# CATv1.net
KiCad netlist of a schematic drawn in EAGLE
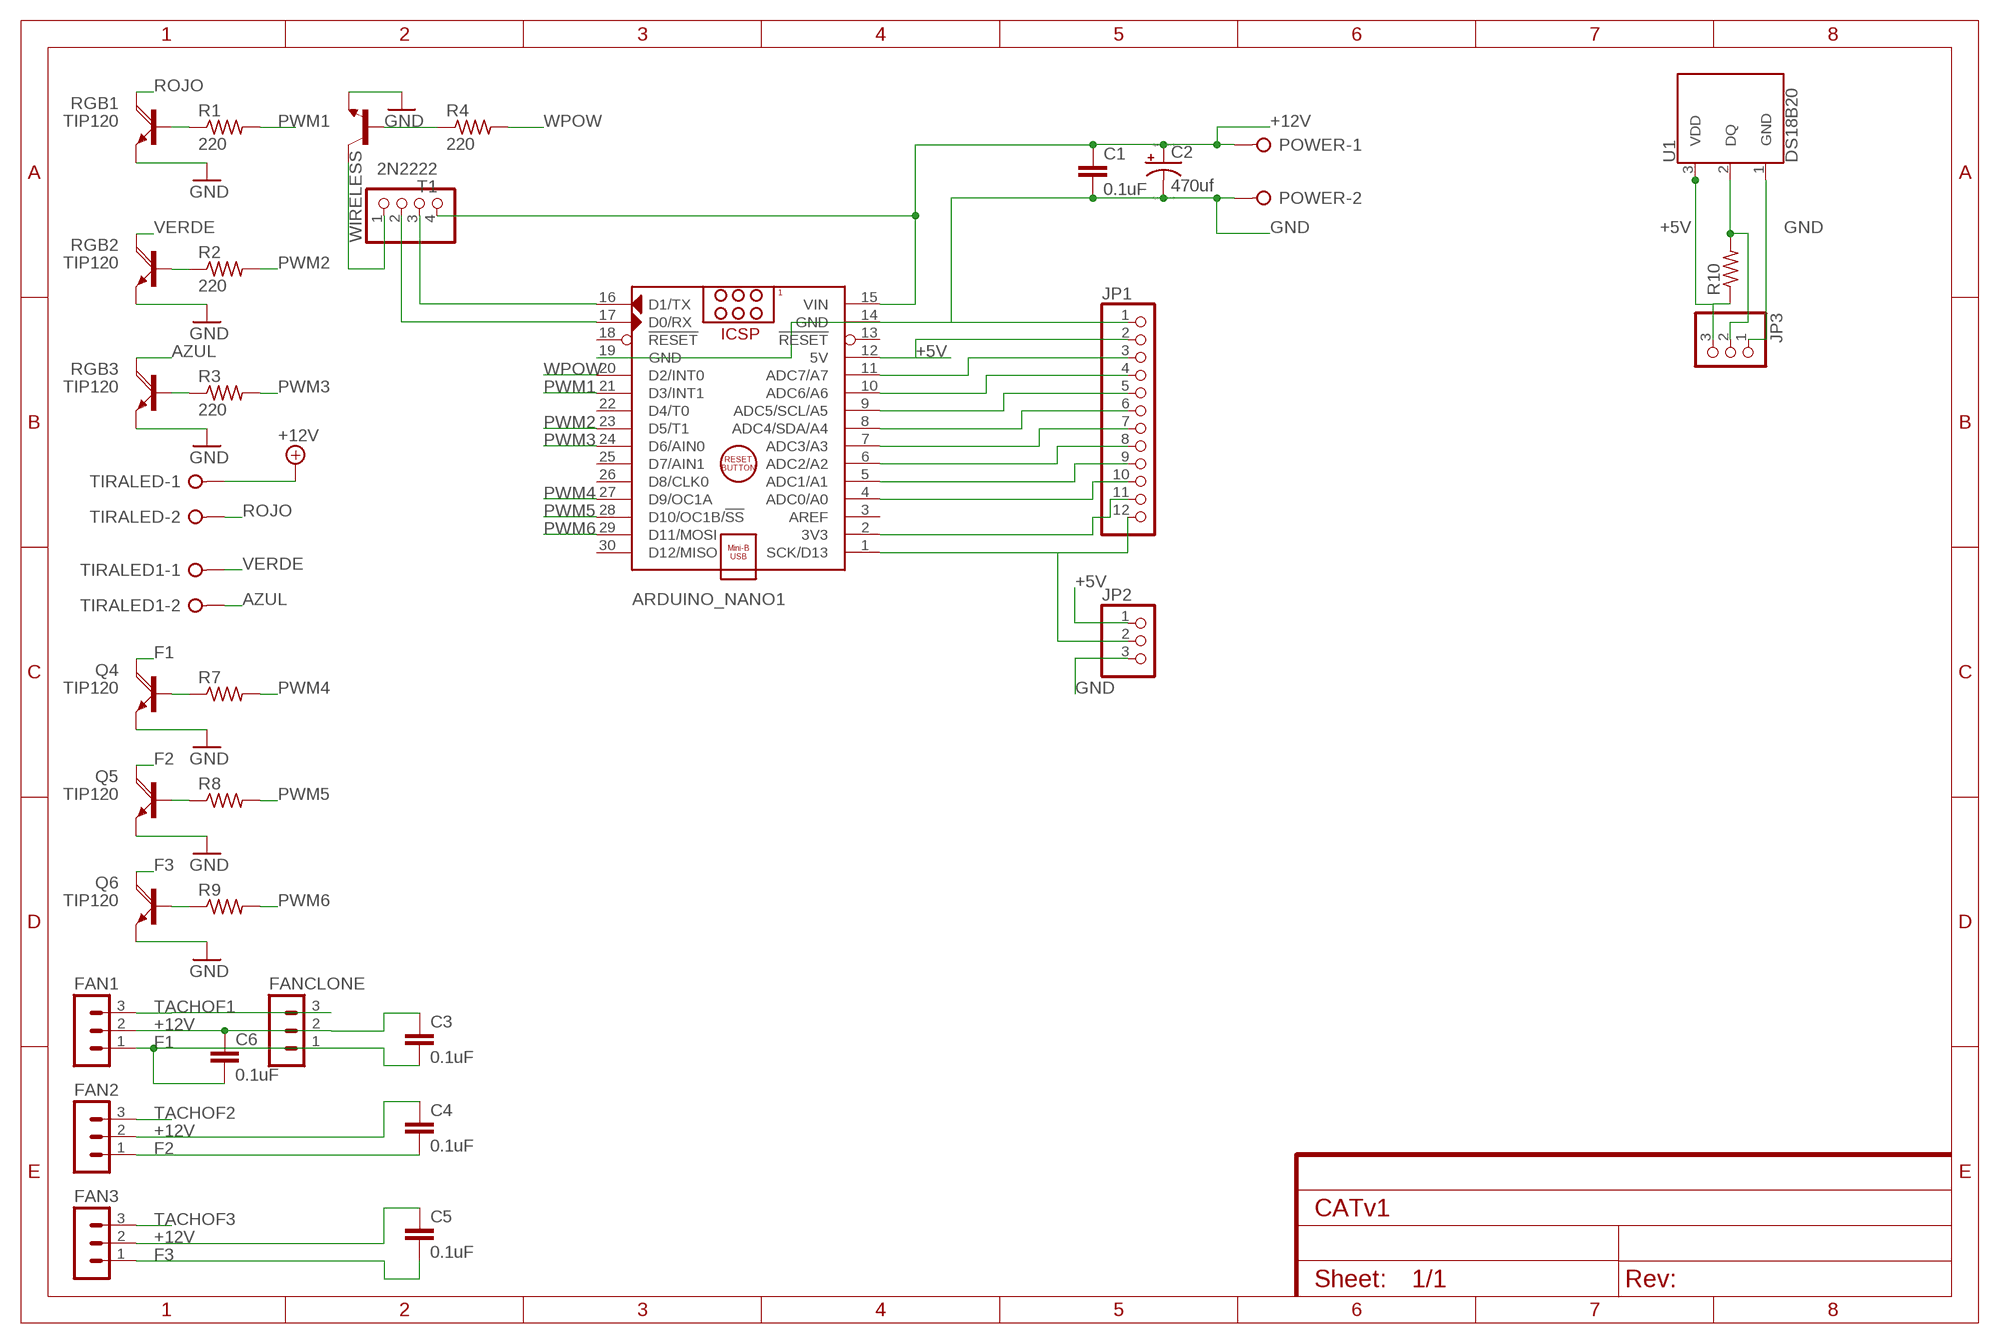
[diagram p0: schematic, sheet 1]

(export (version "E")
  (design (tool "Eeschema 10.0.6"))
  (components
    (comp (ref "ARDUINO_NANO1")
      (value "ARDUINO_NANO")
      (footprint "eagle-import:ARDUINO_NANO")
      (libsource (lib "eagle-import") (part "ARDUINO_NANO"))
    )
    (comp (ref "C1")
      (value "0.1uF")
      (footprint "eagle-import:CAP-PTH-SMALL-KIT")
      (libsource (lib "eagle-import") (part "0.1UF-KIT-EZ-50V-20%"))
    )
    (comp (ref "C2")
      (value "470uf")
      (footprint "eagle-import:E5-10,5")
      (libsource (lib "eagle-import") (part "CPOL-USE5-10.5"))
    )
    (comp (ref "C3")
      (value "0.1uF")
      (footprint "eagle-import:CAP-PTH-SMALL-KIT")
      (libsource (lib "eagle-import") (part "0.1UF-KIT-EZ-50V-20%"))
    )
    (comp (ref "C4")
      (value "0.1uF")
      (footprint "eagle-import:CAP-PTH-SMALL-KIT")
      (libsource (lib "eagle-import") (part "0.1UF-KIT-EZ-50V-20%"))
    )
    (comp (ref "C5")
      (value "0.1uF")
      (footprint "eagle-import:CAP-PTH-SMALL-KIT")
      (libsource (lib "eagle-import") (part "0.1UF-KIT-EZ-50V-20%"))
    )
    (comp (ref "C6")
      (value "0.1uF")
      (footprint "eagle-import:CAP-PTH-SMALL-KIT")
      (libsource (lib "eagle-import") (part "0.1UF-KIT-EZ-50V-20%"))
    )
    (comp (ref "FAN1")
      (value "MA03-1")
      (footprint "eagle-import:MA03-1")
      (libsource (lib "eagle-import") (part "MA03-1"))
    )
    (comp (ref "FAN2")
      (value "MA03-1")
      (footprint "eagle-import:MA03-1")
      (libsource (lib "eagle-import") (part "MA03-1"))
    )
    (comp (ref "FAN3")
      (value "MA03-1")
      (footprint "eagle-import:MA03-1")
      (libsource (lib "eagle-import") (part "MA03-1"))
    )
    (comp (ref "FANCLONE")
      (value "MA03-1")
      (footprint "eagle-import:MA03-1")
      (libsource (lib "eagle-import") (part "MA03-1"))
    )
    (comp (ref "JP1")
      (value "PINHD-1X12")
      (footprint "eagle-import:1X12")
      (libsource (lib "eagle-import") (part "PINHD-1X12"))
    )
    (comp (ref "JP2")
      (value "PINHD-1X3")
      (footprint "eagle-import:1X03")
      (libsource (lib "eagle-import") (part "PINHD-1X3"))
    )
    (comp (ref "JP3")
      (value "PINHD-1X3")
      (footprint "eagle-import:1X03")
      (libsource (lib "eagle-import") (part "PINHD-1X3"))
    )
    (comp (ref "POWER")
      (value "W237-02P")
      (footprint "eagle-import:W237-132")
      (libsource (lib "eagle-import") (part "W237-02P"))
    )
    (comp (ref "Q4")
      (value "TIP120")
      (footprint "eagle-import:TO220AH")
      (libsource (lib "eagle-import") (part "TIP120"))
    )
    (comp (ref "Q5")
      (value "TIP120")
      (footprint "eagle-import:TO220AH")
      (libsource (lib "eagle-import") (part "TIP120"))
    )
    (comp (ref "Q6")
      (value "TIP120")
      (footprint "eagle-import:TO220AH")
      (libsource (lib "eagle-import") (part "TIP120"))
    )
    (comp (ref "R1")
      (value "220")
      (footprint "eagle-import:0207_10")
      (libsource (lib "eagle-import") (part "R-US_0207/10"))
    )
    (comp (ref "R2")
      (value "220")
      (footprint "eagle-import:0207_10")
      (libsource (lib "eagle-import") (part "R-US_0207/10"))
    )
    (comp (ref "R3")
      (value "220")
      (footprint "eagle-import:0207_10")
      (libsource (lib "eagle-import") (part "R-US_0207/10"))
    )
    (comp (ref "R4")
      (value "220")
      (footprint "eagle-import:0207_12")
      (libsource (lib "eagle-import") (part "R-US_0207/12"))
    )
    (comp (ref "R7")
      (value "R-US_0207/10")
      (footprint "eagle-import:0207_10")
      (libsource (lib "eagle-import") (part "R-US_0207/10"))
    )
    (comp (ref "R8")
      (value "R-US_0207/10")
      (footprint "eagle-import:0207_10")
      (libsource (lib "eagle-import") (part "R-US_0207/10"))
    )
    (comp (ref "R9")
      (value "R-US_0207/10")
      (footprint "eagle-import:0207_10")
      (libsource (lib "eagle-import") (part "R-US_0207/10"))
    )
    (comp (ref "R10")
      (value "R-US_0207/10")
      (footprint "eagle-import:0207_10")
      (libsource (lib "eagle-import") (part "R-US_0207/10"))
    )
    (comp (ref "RGB1")
      (value "TIP120")
      (footprint "eagle-import:TO220AH")
      (libsource (lib "eagle-import") (part "TIP120"))
    )
    (comp (ref "RGB2")
      (value "TIP120")
      (footprint "eagle-import:TO220AH")
      (libsource (lib "eagle-import") (part "TIP120"))
    )
    (comp (ref "RGB3")
      (value "TIP120")
      (footprint "eagle-import:TO220AH")
      (libsource (lib "eagle-import") (part "TIP120"))
    )
    (comp (ref "T1")
      (value "2N2222")
      (footprint "eagle-import:TO92-EBC-OVAL")
      (libsource (lib "eagle-import") (part "2N2222"))
    )
    (comp (ref "TIRALED")
      (value "W237-02P")
      (footprint "eagle-import:W237-132")
      (libsource (lib "eagle-import") (part "W237-02P"))
    )
    (comp (ref "TIRALED1")
      (value "W237-02P")
      (footprint "eagle-import:W237-132")
      (libsource (lib "eagle-import") (part "W237-02P"))
    )
    (comp (ref "U1")
      (value "DS18B20")
      (footprint "eagle-import:TO-92-AMMO")
      (libsource (lib "eagle-import") (part "DS18B20"))
    )
    (comp (ref "WIRELESS")
      (value "PINHD-1X4")
      (footprint "eagle-import:1X04")
      (libsource (lib "eagle-import") (part "PINHD-1X4"))
    )
  )
  (nets
    (net (code "1") (name "+12V") (class "Default")
      (node (ref "ARDUINO_NANO1") (pin "15") (pinfunction "VIN_15") (pintype "power_in"))
      (node (ref "C1") (pin "1") (pinfunction "1_1") (pintype "passive"))
      (node (ref "C2") (pin "+") (pinfunction "+_+") (pintype "passive"))
      (node (ref "C3") (pin "1") (pinfunction "1_1") (pintype "passive"))
      (node (ref "C4") (pin "1") (pinfunction "1_1") (pintype "passive"))
      (node (ref "C5") (pin "1") (pinfunction "1_1") (pintype "passive"))
      (node (ref "C6") (pin "1") (pinfunction "1_1") (pintype "passive"))
      (node (ref "FAN1") (pin "2") (pinfunction "2_2") (pintype "passive"))
      (node (ref "FAN2") (pin "2") (pinfunction "2_2") (pintype "passive"))
      (node (ref "FAN3") (pin "2") (pinfunction "2_2") (pintype "passive"))
      (node (ref "FANCLONE") (pin "2") (pinfunction "2_2") (pintype "passive"))
      (node (ref "POWER") (pin "1") (pinfunction "KL_1") (pintype "passive"))
      (node (ref "TIRALED") (pin "1") (pinfunction "KL_1") (pintype "passive"))
      (node (ref "WIRELESS") (pin "4") (pinfunction "4_4") (pintype "passive"))
    )
    (net (code "2") (name "/+5V") (class "Default")
      (node (ref "ARDUINO_NANO1") (pin "12") (pinfunction "5V_12") (pintype "power_in"))
      (node (ref "JP1") (pin "2") (pinfunction "2_2") (pintype "passive"))
      (node (ref "JP2") (pin "1") (pinfunction "1_1") (pintype "passive"))
      (node (ref "JP3") (pin "3") (pinfunction "3_3") (pintype "passive"))
      (node (ref "R10") (pin "1") (pinfunction "1_1") (pintype "passive"))
      (node (ref "U1") (pin "3") (pinfunction "VDD_3") (pintype "power_in"))
    )
    (net (code "3") (name "/AZUL") (class "Default")
      (node (ref "RGB3") (pin "C") (pinfunction "C_C") (pintype "passive"))
      (node (ref "TIRALED1") (pin "2") (pinfunction "KL_2") (pintype "passive"))
    )
    (net (code "4") (name "/F1") (class "Default")
      (node (ref "C3") (pin "2") (pinfunction "2_2") (pintype "passive"))
      (node (ref "C6") (pin "2") (pinfunction "2_2") (pintype "passive"))
      (node (ref "FAN1") (pin "1") (pinfunction "1_1") (pintype "passive"))
      (node (ref "FANCLONE") (pin "1") (pinfunction "1_1") (pintype "passive"))
      (node (ref "Q4") (pin "C") (pinfunction "C_C") (pintype "passive"))
    )
    (net (code "5") (name "/F2") (class "Default")
      (node (ref "C4") (pin "2") (pinfunction "2_2") (pintype "passive"))
      (node (ref "FAN2") (pin "1") (pinfunction "1_1") (pintype "passive"))
      (node (ref "Q5") (pin "C") (pinfunction "C_C") (pintype "passive"))
    )
    (net (code "6") (name "/F3") (class "Default")
      (node (ref "C5") (pin "2") (pinfunction "2_2") (pintype "passive"))
      (node (ref "FAN3") (pin "1") (pinfunction "1_1") (pintype "passive"))
      (node (ref "Q6") (pin "C") (pinfunction "C_C") (pintype "passive"))
    )
    (net (code "7") (name "/PWM1") (class "Default")
      (node (ref "ARDUINO_NANO1") (pin "21") (pinfunction "D3/INT1_21") (pintype "bidirectional"))
      (node (ref "R1") (pin "2") (pinfunction "2_2") (pintype "passive"))
    )
    (net (code "8") (name "/PWM2") (class "Default")
      (node (ref "ARDUINO_NANO1") (pin "23") (pinfunction "D5/T1_23") (pintype "bidirectional"))
      (node (ref "R2") (pin "2") (pinfunction "2_2") (pintype "passive"))
    )
    (net (code "9") (name "/PWM3") (class "Default")
      (node (ref "ARDUINO_NANO1") (pin "24") (pinfunction "D6/AIN0_24") (pintype "bidirectional"))
      (node (ref "R3") (pin "2") (pinfunction "2_2") (pintype "passive"))
    )
    (net (code "10") (name "/PWM4") (class "Default")
      (node (ref "ARDUINO_NANO1") (pin "27") (pinfunction "D9/OC1A_27") (pintype "bidirectional"))
      (node (ref "R7") (pin "2") (pinfunction "2_2") (pintype "passive"))
    )
    (net (code "11") (name "/PWM5") (class "Default")
      (node (ref "ARDUINO_NANO1") (pin "28") (pinfunction "D10/OC1B/~{SS}_28") (pintype "bidirectional"))
      (node (ref "R8") (pin "2") (pinfunction "2_2") (pintype "passive"))
    )
    (net (code "12") (name "/PWM6") (class "Default")
      (node (ref "ARDUINO_NANO1") (pin "29") (pinfunction "D11/MOSI_29") (pintype "bidirectional"))
      (node (ref "R9") (pin "2") (pinfunction "2_2") (pintype "passive"))
    )
    (net (code "13") (name "/ROJO") (class "Default")
      (node (ref "RGB1") (pin "C") (pinfunction "C_C") (pintype "passive"))
      (node (ref "TIRALED") (pin "2") (pinfunction "KL_2") (pintype "passive"))
    )
    (net (code "14") (name "/TACHOF1") (class "Default")
      (node (ref "FAN1") (pin "3") (pinfunction "3_3") (pintype "passive"))
      (node (ref "FANCLONE") (pin "3") (pinfunction "3_3") (pintype "passive"))
    )
    (net (code "15") (name "/TACHOF2") (class "Default")
      (node (ref "FAN2") (pin "3") (pinfunction "3_3") (pintype "passive"))
    )
    (net (code "16") (name "/TACHOF3") (class "Default")
      (node (ref "FAN3") (pin "3") (pinfunction "3_3") (pintype "passive"))
    )
    (net (code "17") (name "/VERDE") (class "Default")
      (node (ref "RGB2") (pin "C") (pinfunction "C_C") (pintype "passive"))
      (node (ref "TIRALED1") (pin "1") (pinfunction "KL_1") (pintype "passive"))
    )
    (net (code "18") (name "/WPOW") (class "Default")
      (node (ref "ARDUINO_NANO1") (pin "20") (pinfunction "D2/INT0_20") (pintype "bidirectional"))
      (node (ref "R4") (pin "2") (pinfunction "2_2") (pintype "passive"))
    )
    (net (code "19") (name "GND") (class "Default")
      (node (ref "ARDUINO_NANO1") (pin "14") (pinfunction "GND_14") (pintype "power_in"))
      (node (ref "ARDUINO_NANO1") (pin "19") (pinfunction "GND_19") (pintype "power_in"))
      (node (ref "C1") (pin "2") (pinfunction "2_2") (pintype "passive"))
      (node (ref "C2") (pin "-") (pinfunction "-_-") (pintype "passive"))
      (node (ref "JP1") (pin "1") (pinfunction "1_1") (pintype "passive"))
      (node (ref "JP2") (pin "3") (pinfunction "3_3") (pintype "passive"))
      (node (ref "JP3") (pin "1") (pinfunction "1_1") (pintype "passive"))
      (node (ref "POWER") (pin "2") (pinfunction "KL_2") (pintype "passive"))
      (node (ref "Q4") (pin "E") (pinfunction "E_E") (pintype "passive"))
      (node (ref "Q5") (pin "E") (pinfunction "E_E") (pintype "passive"))
      (node (ref "Q6") (pin "E") (pinfunction "E_E") (pintype "passive"))
      (node (ref "RGB1") (pin "E") (pinfunction "E_E") (pintype "passive"))
      (node (ref "RGB2") (pin "E") (pinfunction "E_E") (pintype "passive"))
      (node (ref "RGB3") (pin "E") (pinfunction "E_E") (pintype "passive"))
      (node (ref "T1") (pin "E") (pinfunction "E_E") (pintype "passive"))
      (node (ref "U1") (pin "1") (pinfunction "GND_1") (pintype "power_in"))
    )
    (net (code "20") (name "Net-(ARDUINO_NANO1-3V3)") (class "Default")
      (node (ref "ARDUINO_NANO1") (pin "2") (pinfunction "3V3_2") (pintype "output"))
      (node (ref "JP1") (pin "11") (pinfunction "11_11") (pintype "passive"))
    )
    (net (code "21") (name "Net-(ARDUINO_NANO1-ADC0{slash}A0)") (class "Default")
      (node (ref "ARDUINO_NANO1") (pin "4") (pinfunction "ADC0/A0_4") (pintype "bidirectional"))
      (node (ref "JP1") (pin "10") (pinfunction "10_10") (pintype "passive"))
    )
    (net (code "22") (name "Net-(ARDUINO_NANO1-ADC1{slash}A1)") (class "Default")
      (node (ref "ARDUINO_NANO1") (pin "5") (pinfunction "ADC1/A1_5") (pintype "bidirectional"))
      (node (ref "JP1") (pin "9") (pinfunction "9_9") (pintype "passive"))
    )
    (net (code "23") (name "Net-(ARDUINO_NANO1-ADC2{slash}A2)") (class "Default")
      (node (ref "ARDUINO_NANO1") (pin "6") (pinfunction "ADC2/A2_6") (pintype "bidirectional"))
      (node (ref "JP1") (pin "8") (pinfunction "8_8") (pintype "passive"))
    )
    (net (code "24") (name "Net-(ARDUINO_NANO1-ADC3{slash}A3)") (class "Default")
      (node (ref "ARDUINO_NANO1") (pin "7") (pinfunction "ADC3/A3_7") (pintype "bidirectional"))
      (node (ref "JP1") (pin "7") (pinfunction "7_7") (pintype "passive"))
    )
    (net (code "25") (name "Net-(ARDUINO_NANO1-ADC4{slash}SDA{slash}A4)") (class "Default")
      (node (ref "ARDUINO_NANO1") (pin "8") (pinfunction "ADC4/SDA/A4_8") (pintype "bidirectional"))
      (node (ref "JP1") (pin "6") (pinfunction "6_6") (pintype "passive"))
    )
    (net (code "26") (name "Net-(ARDUINO_NANO1-ADC5{slash}SCL{slash}A5)") (class "Default")
      (node (ref "ARDUINO_NANO1") (pin "9") (pinfunction "ADC5/SCL/A5_9") (pintype "bidirectional"))
      (node (ref "JP1") (pin "5") (pinfunction "5_5") (pintype "passive"))
    )
    (net (code "27") (name "Net-(ARDUINO_NANO1-ADC6{slash}A6)") (class "Default")
      (node (ref "ARDUINO_NANO1") (pin "10") (pinfunction "ADC6/A6_10") (pintype "bidirectional"))
      (node (ref "JP1") (pin "4") (pinfunction "4_4") (pintype "passive"))
    )
    (net (code "28") (name "Net-(ARDUINO_NANO1-ADC7{slash}A7)") (class "Default")
      (node (ref "ARDUINO_NANO1") (pin "11") (pinfunction "ADC7/A7_11") (pintype "bidirectional"))
      (node (ref "JP1") (pin "3") (pinfunction "3_3") (pintype "passive"))
    )
    (net (code "29") (name "Net-(ARDUINO_NANO1-D0{slash}RX)") (class "Default")
      (node (ref "ARDUINO_NANO1") (pin "17") (pinfunction "D0/RX_17") (pintype "bidirectional"))
      (node (ref "WIRELESS") (pin "2") (pinfunction "2_2") (pintype "passive"))
    )
    (net (code "30") (name "Net-(ARDUINO_NANO1-D1{slash}TX)") (class "Default")
      (node (ref "ARDUINO_NANO1") (pin "16") (pinfunction "D1/TX_16") (pintype "bidirectional"))
      (node (ref "WIRELESS") (pin "3") (pinfunction "3_3") (pintype "passive"))
    )
    (net (code "31") (name "Net-(ARDUINO_NANO1-SCK{slash}D13)") (class "Default")
      (node (ref "ARDUINO_NANO1") (pin "1") (pinfunction "SCK/D13_1") (pintype "bidirectional"))
      (node (ref "JP1") (pin "12") (pinfunction "12_12") (pintype "passive"))
      (node (ref "JP2") (pin "2") (pinfunction "2_2") (pintype "passive"))
    )
    (net (code "32") (name "Net-(Q4-PadB)") (class "Default")
      (node (ref "Q4") (pin "B") (pinfunction "B_B") (pintype "passive"))
      (node (ref "R7") (pin "1") (pinfunction "1_1") (pintype "passive"))
    )
    (net (code "33") (name "Net-(Q5-PadB)") (class "Default")
      (node (ref "Q5") (pin "B") (pinfunction "B_B") (pintype "passive"))
      (node (ref "R8") (pin "1") (pinfunction "1_1") (pintype "passive"))
    )
    (net (code "34") (name "Net-(Q6-PadB)") (class "Default")
      (node (ref "Q6") (pin "B") (pinfunction "B_B") (pintype "passive"))
      (node (ref "R9") (pin "1") (pinfunction "1_1") (pintype "passive"))
    )
    (net (code "35") (name "Net-(R1-Pad1)") (class "Default")
      (node (ref "R1") (pin "1") (pinfunction "1_1") (pintype "passive"))
      (node (ref "RGB1") (pin "B") (pinfunction "B_B") (pintype "passive"))
    )
    (net (code "36") (name "Net-(R2-Pad1)") (class "Default")
      (node (ref "R2") (pin "1") (pinfunction "1_1") (pintype "passive"))
      (node (ref "RGB2") (pin "B") (pinfunction "B_B") (pintype "passive"))
    )
    (net (code "37") (name "Net-(R3-Pad1)") (class "Default")
      (node (ref "R3") (pin "1") (pinfunction "1_1") (pintype "passive"))
      (node (ref "RGB3") (pin "B") (pinfunction "B_B") (pintype "passive"))
    )
    (net (code "38") (name "Net-(R4-Pad1)") (class "Default")
      (node (ref "R4") (pin "1") (pinfunction "1_1") (pintype "passive"))
      (node (ref "T1") (pin "B") (pinfunction "B_B") (pintype "passive"))
    )
    (net (code "39") (name "Net-(T1-PadC)") (class "Default")
      (node (ref "T1") (pin "C") (pinfunction "C_C") (pintype "passive"))
      (node (ref "WIRELESS") (pin "1") (pinfunction "1_1") (pintype "passive"))
    )
    (net (code "40") (name "Net-(U1-DQ)") (class "Default")
      (node (ref "JP3") (pin "2") (pinfunction "2_2") (pintype "passive"))
      (node (ref "R10") (pin "2") (pinfunction "2_2") (pintype "passive"))
      (node (ref "U1") (pin "2") (pinfunction "DQ_2") (pintype "bidirectional"))
    )
    (net (code "41") (name "unconnected-(ARDUINO_NANO1-AREF-Pad3)") (class "Default")
      (node (ref "ARDUINO_NANO1") (pin "3") (pinfunction "AREF_3") (pintype "input"))
    )
    (net (code "42") (name "unconnected-(ARDUINO_NANO1-D4{slash}T0-Pad22)") (class "Default")
      (node (ref "ARDUINO_NANO1") (pin "22") (pinfunction "D4/T0_22") (pintype "bidirectional"))
    )
    (net (code "43") (name "unconnected-(ARDUINO_NANO1-D7{slash}AIN1-Pad25)") (class "Default")
      (node (ref "ARDUINO_NANO1") (pin "25") (pinfunction "D7/AIN1_25") (pintype "bidirectional"))
    )
    (net (code "44") (name "unconnected-(ARDUINO_NANO1-D8{slash}CLK0-Pad26)") (class "Default")
      (node (ref "ARDUINO_NANO1") (pin "26") (pinfunction "D8/CLK0_26") (pintype "bidirectional"))
    )
    (net (code "45") (name "unconnected-(ARDUINO_NANO1-D12{slash}MISO-Pad30)") (class "Default")
      (node (ref "ARDUINO_NANO1") (pin "30") (pinfunction "D12/MISO_30") (pintype "bidirectional"))
    )
    (net (code "46") (name "unconnected-(ARDUINO_NANO1-~{RESET}-Pad13)") (class "Default")
      (node (ref "ARDUINO_NANO1") (pin "13") (pinfunction "~{RESET}_13") (pintype "input"))
    )
    (net (code "47") (name "unconnected-(ARDUINO_NANO1-~{RESET}-Pad18)") (class "Default")
      (node (ref "ARDUINO_NANO1") (pin "18") (pinfunction "~{RESET}_18") (pintype "input"))
    )
  )
)
